# relay-attentuator.net
KiCad netlist of a schematic drawn in EAGLE
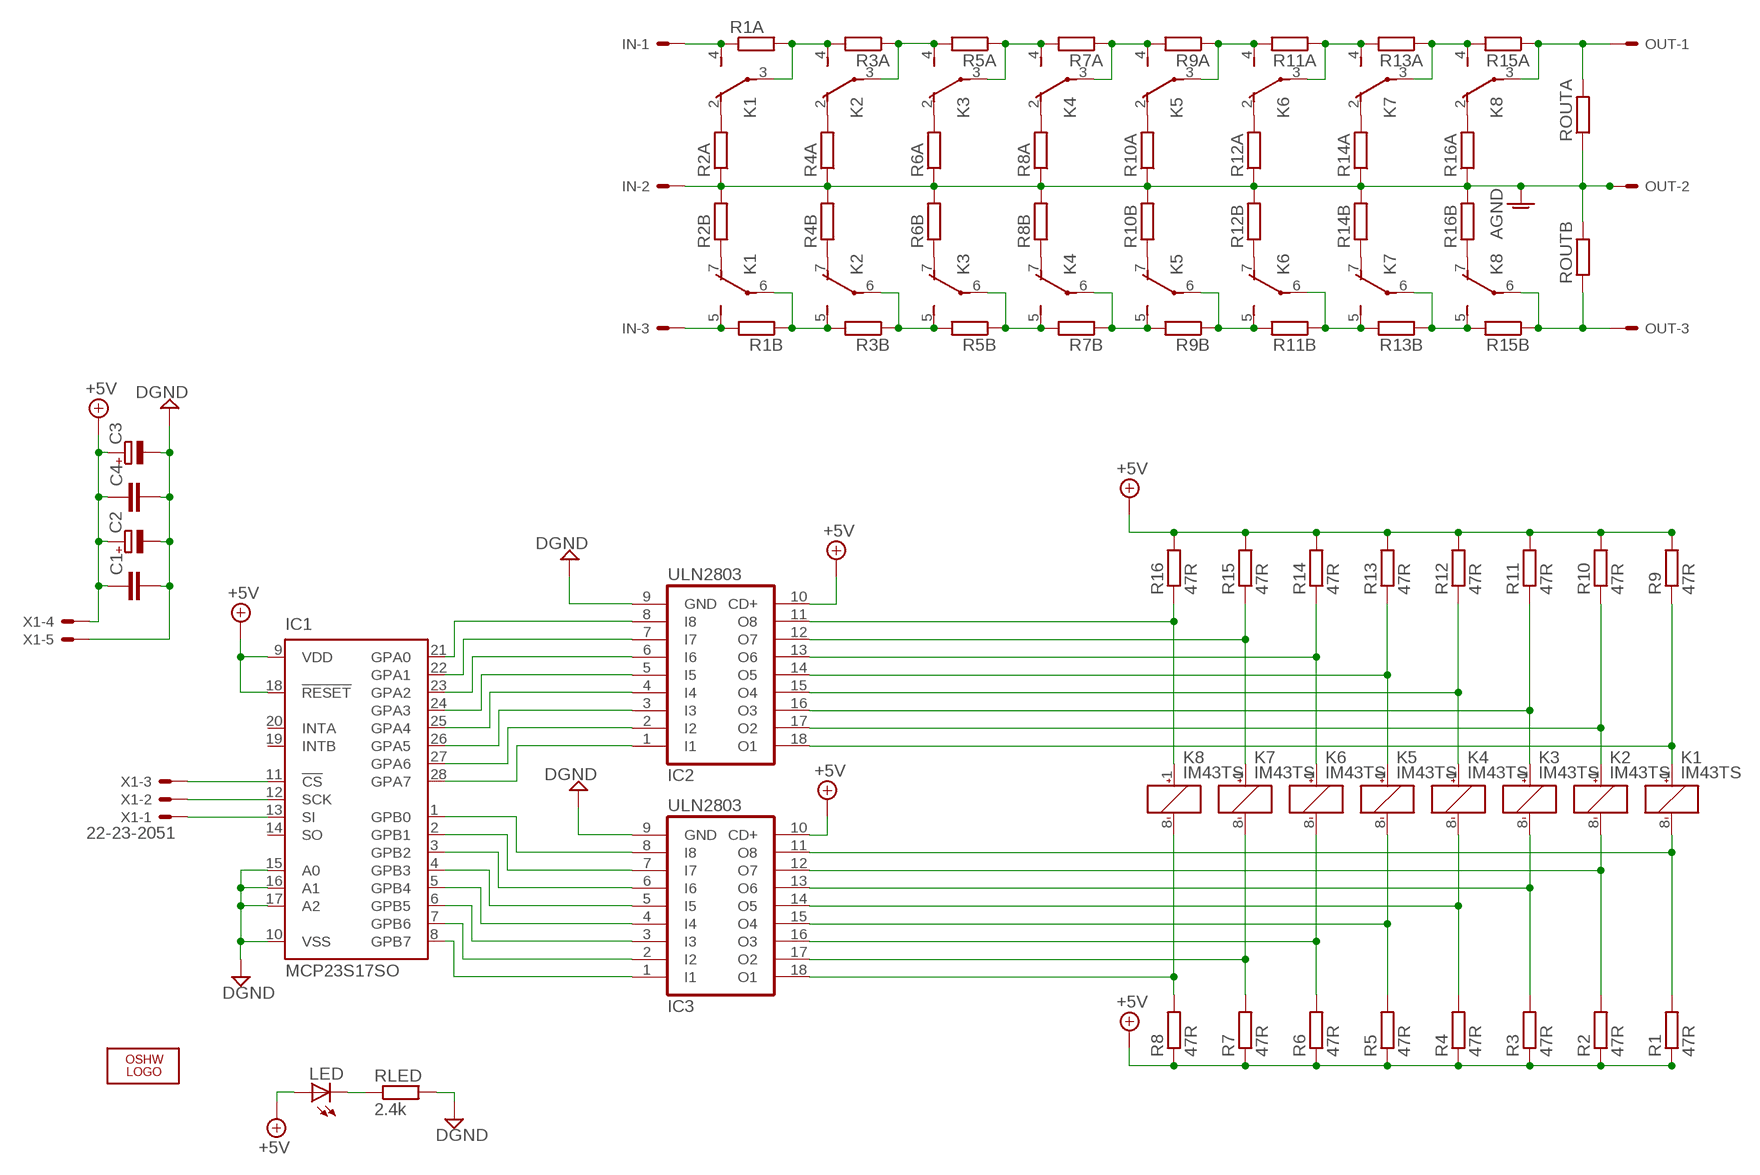
[diagram p0: schematic, sheet 1]

(export (version "E")
  (design (tool "Eeschema 10.0.6"))
  (components
    (comp (ref "C1")
      (value "C-EUC1206")
      (footprint "eagle-import:C1206")
      (libsource (lib "eagle-import") (part "C-EUC1206"))
    )
    (comp (ref "C2")
      (value "CPOL-EUE3.5-8")
      (footprint "eagle-import:E3,5-8")
      (libsource (lib "eagle-import") (part "CPOL-EUE3.5-8"))
    )
    (comp (ref "C3")
      (value "CPOL-EUE3.5-8")
      (footprint "eagle-import:E3,5-8")
      (libsource (lib "eagle-import") (part "CPOL-EUE3.5-8"))
    )
    (comp (ref "C4")
      (value "C-EUC1206")
      (footprint "eagle-import:C1206")
      (libsource (lib "eagle-import") (part "C-EUC1206"))
    )
    (comp (ref "IC1")
      (value "MCP23S17SO")
      (footprint "eagle-import:SO28W")
      (fields (field (name "MF") "MICROCHIP") (field (name "MPN") "MCP23S17-E/SO"))
      (libsource (lib "eagle-import") (part "MCP23S17SO"))
    )
    (comp (ref "IC2")
      (value "ULN2803")
      (footprint "eagle-import:SO-18W")
      (libsource (lib "eagle-import") (part "ULN2803ADW"))
    )
    (comp (ref "IC3")
      (value "ULN2803")
      (footprint "eagle-import:SO-18W")
      (libsource (lib "eagle-import") (part "ULN2803ADW"))
    )
    (comp (ref "IN")
      (value "22-23-2031")
      (footprint "eagle-import:22-23-2031")
      (libsource (lib "eagle-import") (part "22-23-2031"))
    )
    (comp (ref "K1")
      (value "IM43TS")
      (footprint "eagle-import:IM43TS")
      (libsource (lib "eagle-import") (part "IM43TS"))
    )
    (comp (ref "K2")
      (value "IM43TS")
      (footprint "eagle-import:IM43TS")
      (libsource (lib "eagle-import") (part "IM43TS"))
    )
    (comp (ref "K3")
      (value "IM43TS")
      (footprint "eagle-import:IM43TS")
      (libsource (lib "eagle-import") (part "IM43TS"))
    )
    (comp (ref "K4")
      (value "IM43TS")
      (footprint "eagle-import:IM43TS")
      (libsource (lib "eagle-import") (part "IM43TS"))
    )
    (comp (ref "K5")
      (value "IM43TS")
      (footprint "eagle-import:IM43TS")
      (libsource (lib "eagle-import") (part "IM43TS"))
    )
    (comp (ref "K6")
      (value "IM43TS")
      (footprint "eagle-import:IM43TS")
      (libsource (lib "eagle-import") (part "IM43TS"))
    )
    (comp (ref "K7")
      (value "IM43TS")
      (footprint "eagle-import:IM43TS")
      (libsource (lib "eagle-import") (part "IM43TS"))
    )
    (comp (ref "K8")
      (value "IM43TS")
      (footprint "eagle-import:IM43TS")
      (libsource (lib "eagle-import") (part "IM43TS"))
    )
    (comp (ref "LED")
      (value "LEDCHIPLED_1206")
      (footprint "eagle-import:CHIPLED_1206")
      (libsource (lib "eagle-import") (part "LEDCHIPLED_1206"))
    )
    (comp (ref "LOGO1")
      (value "OSHW_LOGO_FILLX0200-NT")
      (footprint "eagle-import:OSHW_FILLX200_NOTEXT")
      (libsource (lib "eagle-import") (part "OSHW_LOGO_FILLX0200-NT"))
    )
    (comp (ref "OUT")
      (value "22-23-2031")
      (footprint "eagle-import:22-23-2031")
      (libsource (lib "eagle-import") (part "22-23-2031"))
    )
    (comp (ref "R1")
      (value "47R")
      (footprint "eagle-import:R1206")
      (libsource (lib "eagle-import") (part "R-EU_R1206"))
    )
    (comp (ref "R1A")
      (value "R-EU_R1206")
      (footprint "eagle-import:R1206")
      (libsource (lib "eagle-import") (part "R-EU_R1206"))
    )
    (comp (ref "R1B")
      (value "R-EU_R1206")
      (footprint "eagle-import:R1206")
      (libsource (lib "eagle-import") (part "R-EU_R1206"))
    )
    (comp (ref "R2")
      (value "47R")
      (footprint "eagle-import:R1206")
      (libsource (lib "eagle-import") (part "R-EU_R1206"))
    )
    (comp (ref "R2A")
      (value "R-EU_R1206")
      (footprint "eagle-import:R1206")
      (libsource (lib "eagle-import") (part "R-EU_R1206"))
    )
    (comp (ref "R2B")
      (value "R-EU_R1206")
      (footprint "eagle-import:R1206")
      (libsource (lib "eagle-import") (part "R-EU_R1206"))
    )
    (comp (ref "R3")
      (value "47R")
      (footprint "eagle-import:R1206")
      (libsource (lib "eagle-import") (part "R-EU_R1206"))
    )
    (comp (ref "R3A")
      (value "R-EU_R1206")
      (footprint "eagle-import:R1206")
      (libsource (lib "eagle-import") (part "R-EU_R1206"))
    )
    (comp (ref "R3B")
      (value "R-EU_R1206")
      (footprint "eagle-import:R1206")
      (libsource (lib "eagle-import") (part "R-EU_R1206"))
    )
    (comp (ref "R4")
      (value "47R")
      (footprint "eagle-import:R1206")
      (libsource (lib "eagle-import") (part "R-EU_R1206"))
    )
    (comp (ref "R4A")
      (value "R-EU_R1206")
      (footprint "eagle-import:R1206")
      (libsource (lib "eagle-import") (part "R-EU_R1206"))
    )
    (comp (ref "R4B")
      (value "R-EU_R1206")
      (footprint "eagle-import:R1206")
      (libsource (lib "eagle-import") (part "R-EU_R1206"))
    )
    (comp (ref "R5")
      (value "47R")
      (footprint "eagle-import:R1206")
      (libsource (lib "eagle-import") (part "R-EU_R1206"))
    )
    (comp (ref "R5A")
      (value "R-EU_R1206")
      (footprint "eagle-import:R1206")
      (libsource (lib "eagle-import") (part "R-EU_R1206"))
    )
    (comp (ref "R5B")
      (value "R-EU_R1206")
      (footprint "eagle-import:R1206")
      (libsource (lib "eagle-import") (part "R-EU_R1206"))
    )
    (comp (ref "R6")
      (value "47R")
      (footprint "eagle-import:R1206")
      (libsource (lib "eagle-import") (part "R-EU_R1206"))
    )
    (comp (ref "R6A")
      (value "R-EU_R1206")
      (footprint "eagle-import:R1206")
      (libsource (lib "eagle-import") (part "R-EU_R1206"))
    )
    (comp (ref "R6B")
      (value "R-EU_R1206")
      (footprint "eagle-import:R1206")
      (libsource (lib "eagle-import") (part "R-EU_R1206"))
    )
    (comp (ref "R7")
      (value "47R")
      (footprint "eagle-import:R1206")
      (libsource (lib "eagle-import") (part "R-EU_R1206"))
    )
    (comp (ref "R7A")
      (value "R-EU_R1206")
      (footprint "eagle-import:R1206")
      (libsource (lib "eagle-import") (part "R-EU_R1206"))
    )
    (comp (ref "R7B")
      (value "R-EU_R1206")
      (footprint "eagle-import:R1206")
      (libsource (lib "eagle-import") (part "R-EU_R1206"))
    )
    (comp (ref "R8")
      (value "47R")
      (footprint "eagle-import:R1206")
      (libsource (lib "eagle-import") (part "R-EU_R1206"))
    )
    (comp (ref "R8A")
      (value "R-EU_R1206")
      (footprint "eagle-import:R1206")
      (libsource (lib "eagle-import") (part "R-EU_R1206"))
    )
    (comp (ref "R8B")
      (value "R-EU_R1206")
      (footprint "eagle-import:R1206")
      (libsource (lib "eagle-import") (part "R-EU_R1206"))
    )
    (comp (ref "R9")
      (value "47R")
      (footprint "eagle-import:R1206")
      (libsource (lib "eagle-import") (part "R-EU_R1206"))
    )
    (comp (ref "R9A")
      (value "R-EU_R1206")
      (footprint "eagle-import:R1206")
      (libsource (lib "eagle-import") (part "R-EU_R1206"))
    )
    (comp (ref "R9B")
      (value "R-EU_R1206")
      (footprint "eagle-import:R1206")
      (libsource (lib "eagle-import") (part "R-EU_R1206"))
    )
    (comp (ref "R10")
      (value "47R")
      (footprint "eagle-import:R1206")
      (libsource (lib "eagle-import") (part "R-EU_R1206"))
    )
    (comp (ref "R10A")
      (value "R-EU_R1206")
      (footprint "eagle-import:R1206")
      (libsource (lib "eagle-import") (part "R-EU_R1206"))
    )
    (comp (ref "R10B")
      (value "R-EU_R1206")
      (footprint "eagle-import:R1206")
      (libsource (lib "eagle-import") (part "R-EU_R1206"))
    )
    (comp (ref "R11")
      (value "47R")
      (footprint "eagle-import:R1206")
      (libsource (lib "eagle-import") (part "R-EU_R1206"))
    )
    (comp (ref "R11A")
      (value "R-EU_R1206")
      (footprint "eagle-import:R1206")
      (libsource (lib "eagle-import") (part "R-EU_R1206"))
    )
    (comp (ref "R11B")
      (value "R-EU_R1206")
      (footprint "eagle-import:R1206")
      (libsource (lib "eagle-import") (part "R-EU_R1206"))
    )
    (comp (ref "R12")
      (value "47R")
      (footprint "eagle-import:R1206")
      (libsource (lib "eagle-import") (part "R-EU_R1206"))
    )
    (comp (ref "R12A")
      (value "R-EU_R1206")
      (footprint "eagle-import:R1206")
      (libsource (lib "eagle-import") (part "R-EU_R1206"))
    )
    (comp (ref "R12B")
      (value "R-EU_R1206")
      (footprint "eagle-import:R1206")
      (libsource (lib "eagle-import") (part "R-EU_R1206"))
    )
    (comp (ref "R13")
      (value "47R")
      (footprint "eagle-import:R1206")
      (libsource (lib "eagle-import") (part "R-EU_R1206"))
    )
    (comp (ref "R13A")
      (value "R-EU_R1206")
      (footprint "eagle-import:R1206")
      (libsource (lib "eagle-import") (part "R-EU_R1206"))
    )
    (comp (ref "R13B")
      (value "R-EU_R1206")
      (footprint "eagle-import:R1206")
      (libsource (lib "eagle-import") (part "R-EU_R1206"))
    )
    (comp (ref "R14")
      (value "47R")
      (footprint "eagle-import:R1206")
      (libsource (lib "eagle-import") (part "R-EU_R1206"))
    )
    (comp (ref "R14A")
      (value "R-EU_R1206")
      (footprint "eagle-import:R1206")
      (libsource (lib "eagle-import") (part "R-EU_R1206"))
    )
    (comp (ref "R14B")
      (value "R-EU_R1206")
      (footprint "eagle-import:R1206")
      (libsource (lib "eagle-import") (part "R-EU_R1206"))
    )
    (comp (ref "R15")
      (value "47R")
      (footprint "eagle-import:R1206")
      (libsource (lib "eagle-import") (part "R-EU_R1206"))
    )
    (comp (ref "R15A")
      (value "R-EU_R1206")
      (footprint "eagle-import:R1206")
      (libsource (lib "eagle-import") (part "R-EU_R1206"))
    )
    (comp (ref "R15B")
      (value "R-EU_R1206")
      (footprint "eagle-import:R1206")
      (libsource (lib "eagle-import") (part "R-EU_R1206"))
    )
    (comp (ref "R16")
      (value "47R")
      (footprint "eagle-import:R1206")
      (libsource (lib "eagle-import") (part "R-EU_R1206"))
    )
    (comp (ref "R16A")
      (value "R-EU_R1206")
      (footprint "eagle-import:R1206")
      (libsource (lib "eagle-import") (part "R-EU_R1206"))
    )
    (comp (ref "R16B")
      (value "R-EU_R1206")
      (footprint "eagle-import:R1206")
      (libsource (lib "eagle-import") (part "R-EU_R1206"))
    )
    (comp (ref "RLED")
      (value "2.4k")
      (footprint "eagle-import:R1206")
      (libsource (lib "eagle-import") (part "R-EU_R1206"))
    )
    (comp (ref "ROUTA")
      (value "R-EU_R1206")
      (footprint "eagle-import:R1206")
      (libsource (lib "eagle-import") (part "R-EU_R1206"))
    )
    (comp (ref "ROUTB")
      (value "R-EU_R1206")
      (footprint "eagle-import:R1206")
      (libsource (lib "eagle-import") (part "R-EU_R1206"))
    )
    (comp (ref "X1")
      (value "22-23-2051")
      (footprint "eagle-import:22-23-2051")
      (fields (field (name "MF") "MOLEX"))
      (libsource (lib "eagle-import") (part "22-23-2051"))
    )
  )
  (nets
    (net (code "1") (name "+5V") (class "Default")
      (node (ref "C1") (pin "1") (pinfunction "1_1") (pintype "passive"))
      (node (ref "C2") (pin "+") (pinfunction "+_+") (pintype "passive"))
      (node (ref "C3") (pin "+") (pinfunction "+_+") (pintype "passive"))
      (node (ref "C4") (pin "1") (pinfunction "1_1") (pintype "passive"))
      (node (ref "IC1") (pin "18") (pinfunction "~{RESET}_18") (pintype "input"))
      (node (ref "IC1") (pin "9") (pinfunction "VDD_9") (pintype "power_in"))
      (node (ref "IC2") (pin "10") (pinfunction "CD+_10") (pintype "passive"))
      (node (ref "IC3") (pin "10") (pinfunction "CD+_10") (pintype "passive"))
      (node (ref "LED") (pin "A") (pinfunction "A_A") (pintype "passive"))
      (node (ref "R1") (pin "1") (pinfunction "1_1") (pintype "passive"))
      (node (ref "R10") (pin "2") (pinfunction "2_2") (pintype "passive"))
      (node (ref "R11") (pin "2") (pinfunction "2_2") (pintype "passive"))
      (node (ref "R12") (pin "2") (pinfunction "2_2") (pintype "passive"))
      (node (ref "R13") (pin "2") (pinfunction "2_2") (pintype "passive"))
      (node (ref "R14") (pin "2") (pinfunction "2_2") (pintype "passive"))
      (node (ref "R15") (pin "2") (pinfunction "2_2") (pintype "passive"))
      (node (ref "R16") (pin "2") (pinfunction "2_2") (pintype "passive"))
      (node (ref "R2") (pin "1") (pinfunction "1_1") (pintype "passive"))
      (node (ref "R3") (pin "1") (pinfunction "1_1") (pintype "passive"))
      (node (ref "R4") (pin "1") (pinfunction "1_1") (pintype "passive"))
      (node (ref "R5") (pin "1") (pinfunction "1_1") (pintype "passive"))
      (node (ref "R6") (pin "1") (pinfunction "1_1") (pintype "passive"))
      (node (ref "R7") (pin "1") (pinfunction "1_1") (pintype "passive"))
      (node (ref "R8") (pin "1") (pinfunction "1_1") (pintype "passive"))
      (node (ref "R9") (pin "2") (pinfunction "2_2") (pintype "passive"))
      (node (ref "X1") (pin "4") (pinfunction "S_4") (pintype "passive"))
    )
    (net (code "2") (name "AGND") (class "Default")
      (node (ref "IN") (pin "2") (pinfunction "S_2") (pintype "passive"))
      (node (ref "OUT") (pin "2") (pinfunction "S_2") (pintype "passive"))
      (node (ref "R10A") (pin "1") (pinfunction "1_1") (pintype "passive"))
      (node (ref "R10B") (pin "2") (pinfunction "2_2") (pintype "passive"))
      (node (ref "R12A") (pin "1") (pinfunction "1_1") (pintype "passive"))
      (node (ref "R12B") (pin "2") (pinfunction "2_2") (pintype "passive"))
      (node (ref "R14A") (pin "1") (pinfunction "1_1") (pintype "passive"))
      (node (ref "R14B") (pin "2") (pinfunction "2_2") (pintype "passive"))
      (node (ref "R16A") (pin "1") (pinfunction "1_1") (pintype "passive"))
      (node (ref "R16B") (pin "2") (pinfunction "2_2") (pintype "passive"))
      (node (ref "R2A") (pin "1") (pinfunction "1_1") (pintype "passive"))
      (node (ref "R2B") (pin "2") (pinfunction "2_2") (pintype "passive"))
      (node (ref "R4A") (pin "1") (pinfunction "1_1") (pintype "passive"))
      (node (ref "R4B") (pin "2") (pinfunction "2_2") (pintype "passive"))
      (node (ref "R6A") (pin "1") (pinfunction "1_1") (pintype "passive"))
      (node (ref "R6B") (pin "2") (pinfunction "2_2") (pintype "passive"))
      (node (ref "R8A") (pin "1") (pinfunction "1_1") (pintype "passive"))
      (node (ref "R8B") (pin "2") (pinfunction "2_2") (pintype "passive"))
      (node (ref "ROUTA") (pin "1") (pinfunction "1_1") (pintype "passive"))
      (node (ref "ROUTB") (pin "2") (pinfunction "2_2") (pintype "passive"))
    )
    (net (code "3") (name "DGND") (class "Default")
      (node (ref "C1") (pin "2") (pinfunction "2_2") (pintype "passive"))
      (node (ref "C2") (pin "-") (pinfunction "-_-") (pintype "passive"))
      (node (ref "C3") (pin "-") (pinfunction "-_-") (pintype "passive"))
      (node (ref "C4") (pin "2") (pinfunction "2_2") (pintype "passive"))
      (node (ref "IC1") (pin "10") (pinfunction "VSS_10") (pintype "power_in"))
      (node (ref "IC1") (pin "15") (pinfunction "A0_15") (pintype "input"))
      (node (ref "IC1") (pin "16") (pinfunction "A1_16") (pintype "input"))
      (node (ref "IC1") (pin "17") (pinfunction "A2_17") (pintype "input"))
      (node (ref "IC2") (pin "9") (pinfunction "GND_9") (pintype "power_in"))
      (node (ref "IC3") (pin "9") (pinfunction "GND_9") (pintype "power_in"))
      (node (ref "RLED") (pin "2") (pinfunction "2_2") (pintype "passive"))
      (node (ref "X1") (pin "5") (pinfunction "S_5") (pintype "passive"))
    )
    (net (code "4") (name "Net-(IC1-GPA0)") (class "Default")
      (node (ref "IC1") (pin "21") (pinfunction "GPA0_21") (pintype "bidirectional"))
      (node (ref "IC2") (pin "8") (pinfunction "I8_8") (pintype "input"))
    )
    (net (code "5") (name "Net-(IC1-GPA1)") (class "Default")
      (node (ref "IC1") (pin "22") (pinfunction "GPA1_22") (pintype "bidirectional"))
      (node (ref "IC2") (pin "7") (pinfunction "I7_7") (pintype "input"))
    )
    (net (code "6") (name "Net-(IC1-GPA2)") (class "Default")
      (node (ref "IC1") (pin "23") (pinfunction "GPA2_23") (pintype "bidirectional"))
      (node (ref "IC2") (pin "6") (pinfunction "I6_6") (pintype "input"))
    )
    (net (code "7") (name "Net-(IC1-GPA3)") (class "Default")
      (node (ref "IC1") (pin "24") (pinfunction "GPA3_24") (pintype "bidirectional"))
      (node (ref "IC2") (pin "5") (pinfunction "I5_5") (pintype "input"))
    )
    (net (code "8") (name "Net-(IC1-GPA4)") (class "Default")
      (node (ref "IC1") (pin "25") (pinfunction "GPA4_25") (pintype "bidirectional"))
      (node (ref "IC2") (pin "4") (pinfunction "I4_4") (pintype "input"))
    )
    (net (code "9") (name "Net-(IC1-GPA5)") (class "Default")
      (node (ref "IC1") (pin "26") (pinfunction "GPA5_26") (pintype "bidirectional"))
      (node (ref "IC2") (pin "3") (pinfunction "I3_3") (pintype "input"))
    )
    (net (code "10") (name "Net-(IC1-GPA6)") (class "Default")
      (node (ref "IC1") (pin "27") (pinfunction "GPA6_27") (pintype "bidirectional"))
      (node (ref "IC2") (pin "2") (pinfunction "I2_2") (pintype "input"))
    )
    (net (code "11") (name "Net-(IC1-GPA7)") (class "Default")
      (node (ref "IC1") (pin "28") (pinfunction "GPA7_28") (pintype "bidirectional"))
      (node (ref "IC2") (pin "1") (pinfunction "I1_1") (pintype "input"))
    )
    (net (code "12") (name "Net-(IC1-GPB0)") (class "Default")
      (node (ref "IC1") (pin "1") (pinfunction "GPB0_1") (pintype "bidirectional"))
      (node (ref "IC3") (pin "8") (pinfunction "I8_8") (pintype "input"))
    )
    (net (code "13") (name "Net-(IC1-GPB1)") (class "Default")
      (node (ref "IC1") (pin "2") (pinfunction "GPB1_2") (pintype "bidirectional"))
      (node (ref "IC3") (pin "7") (pinfunction "I7_7") (pintype "input"))
    )
    (net (code "14") (name "Net-(IC1-GPB2)") (class "Default")
      (node (ref "IC1") (pin "3") (pinfunction "GPB2_3") (pintype "bidirectional"))
      (node (ref "IC3") (pin "6") (pinfunction "I6_6") (pintype "input"))
    )
    (net (code "15") (name "Net-(IC1-GPB3)") (class "Default")
      (node (ref "IC1") (pin "4") (pinfunction "GPB3_4") (pintype "bidirectional"))
      (node (ref "IC3") (pin "5") (pinfunction "I5_5") (pintype "input"))
    )
    (net (code "16") (name "Net-(IC1-GPB4)") (class "Default")
      (node (ref "IC1") (pin "5") (pinfunction "GPB4_5") (pintype "bidirectional"))
      (node (ref "IC3") (pin "4") (pinfunction "I4_4") (pintype "input"))
    )
    (net (code "17") (name "Net-(IC1-GPB5)") (class "Default")
      (node (ref "IC1") (pin "6") (pinfunction "GPB5_6") (pintype "bidirectional"))
      (node (ref "IC3") (pin "3") (pinfunction "I3_3") (pintype "input"))
    )
    (net (code "18") (name "Net-(IC1-GPB6)") (class "Default")
      (node (ref "IC1") (pin "7") (pinfunction "GPB6_7") (pintype "bidirectional"))
      (node (ref "IC3") (pin "2") (pinfunction "I2_2") (pintype "input"))
    )
    (net (code "19") (name "Net-(IC1-GPB7)") (class "Default")
      (node (ref "IC1") (pin "8") (pinfunction "GPB7_8") (pintype "bidirectional"))
      (node (ref "IC3") (pin "1") (pinfunction "I1_1") (pintype "input"))
    )
    (net (code "20") (name "Net-(IC1-SCK)") (class "Default")
      (node (ref "IC1") (pin "12") (pinfunction "SCK_12") (pintype "input"))
      (node (ref "X1") (pin "2") (pinfunction "S_2") (pintype "passive"))
    )
    (net (code "21") (name "Net-(IC1-SI)") (class "Default")
      (node (ref "IC1") (pin "13") (pinfunction "SI_13") (pintype "input"))
      (node (ref "X1") (pin "1") (pinfunction "S_1") (pintype "passive"))
    )
    (net (code "22") (name "Net-(IC1-~{CS})") (class "Default")
      (node (ref "IC1") (pin "11") (pinfunction "~{CS}_11") (pintype "input"))
      (node (ref "X1") (pin "3") (pinfunction "S_3") (pintype "passive"))
    )
    (net (code "23") (name "Net-(IC2-O1)") (class "Default")
      (node (ref "IC2") (pin "18") (pinfunction "O1_18") (pintype "open_collector"))
      (node (ref "K1") (pin "1") (pinfunction "+_1") (pintype "passive"))
      (node (ref "R9") (pin "1") (pinfunction "1_1") (pintype "passive"))
    )
    (net (code "24") (name "Net-(IC2-O2)") (class "Default")
      (node (ref "IC2") (pin "17") (pinfunction "O2_17") (pintype "open_collector"))
      (node (ref "K2") (pin "1") (pinfunction "+_1") (pintype "passive"))
      (node (ref "R10") (pin "1") (pinfunction "1_1") (pintype "passive"))
    )
    (net (code "25") (name "Net-(IC2-O3)") (class "Default")
      (node (ref "IC2") (pin "16") (pinfunction "O3_16") (pintype "open_collector"))
      (node (ref "K3") (pin "1") (pinfunction "+_1") (pintype "passive"))
      (node (ref "R11") (pin "1") (pinfunction "1_1") (pintype "passive"))
    )
    (net (code "26") (name "Net-(IC2-O4)") (class "Default")
      (node (ref "IC2") (pin "15") (pinfunction "O4_15") (pintype "open_collector"))
      (node (ref "K4") (pin "1") (pinfunction "+_1") (pintype "passive"))
      (node (ref "R12") (pin "1") (pinfunction "1_1") (pintype "passive"))
    )
    (net (code "27") (name "Net-(IC2-O5)") (class "Default")
      (node (ref "IC2") (pin "14") (pinfunction "O5_14") (pintype "open_collector"))
      (node (ref "K5") (pin "1") (pinfunction "+_1") (pintype "passive"))
      (node (ref "R13") (pin "1") (pinfunction "1_1") (pintype "passive"))
    )
    (net (code "28") (name "Net-(IC2-O6)") (class "Default")
      (node (ref "IC2") (pin "13") (pinfunction "O6_13") (pintype "open_collector"))
      (node (ref "K6") (pin "1") (pinfunction "+_1") (pintype "passive"))
      (node (ref "R14") (pin "1") (pinfunction "1_1") (pintype "passive"))
    )
    (net (code "29") (name "Net-(IC2-O7)") (class "Default")
      (node (ref "IC2") (pin "12") (pinfunction "O7_12") (pintype "open_collector"))
      (node (ref "K7") (pin "1") (pinfunction "+_1") (pintype "passive"))
      (node (ref "R15") (pin "1") (pinfunction "1_1") (pintype "passive"))
    )
    (net (code "30") (name "Net-(IC2-O8)") (class "Default")
      (node (ref "IC2") (pin "11") (pinfunction "O8_11") (pintype "open_collector"))
      (node (ref "K8") (pin "1") (pinfunction "+_1") (pintype "passive"))
      (node (ref "R16") (pin "1") (pinfunction "1_1") (pintype "passive"))
    )
    (net (code "31") (name "Net-(IC3-O1)") (class "Default")
      (node (ref "IC3") (pin "18") (pinfunction "O1_18") (pintype "open_collector"))
      (node (ref "K8") (pin "8") (pinfunction "-_8") (pintype "passive"))
      (node (ref "R8") (pin "2") (pinfunction "2_2") (pintype "passive"))
    )
    (net (code "32") (name "Net-(IC3-O2)") (class "Default")
      (node (ref "IC3") (pin "17") (pinfunction "O2_17") (pintype "open_collector"))
      (node (ref "K7") (pin "8") (pinfunction "-_8") (pintype "passive"))
      (node (ref "R7") (pin "2") (pinfunction "2_2") (pintype "passive"))
    )
    (net (code "33") (name "Net-(IC3-O3)") (class "Default")
      (node (ref "IC3") (pin "16") (pinfunction "O3_16") (pintype "open_collector"))
      (node (ref "K6") (pin "8") (pinfunction "-_8") (pintype "passive"))
      (node (ref "R6") (pin "2") (pinfunction "2_2") (pintype "passive"))
    )
    (net (code "34") (name "Net-(IC3-O4)") (class "Default")
      (node (ref "IC3") (pin "15") (pinfunction "O4_15") (pintype "open_collector"))
      (node (ref "K5") (pin "8") (pinfunction "-_8") (pintype "passive"))
      (node (ref "R5") (pin "2") (pinfunction "2_2") (pintype "passive"))
    )
    (net (code "35") (name "Net-(IC3-O5)") (class "Default")
      (node (ref "IC3") (pin "14") (pinfunction "O5_14") (pintype "open_collector"))
      (node (ref "K4") (pin "8") (pinfunction "-_8") (pintype "passive"))
      (node (ref "R4") (pin "2") (pinfunction "2_2") (pintype "passive"))
    )
    (net (code "36") (name "Net-(IC3-O6)") (class "Default")
      (node (ref "IC3") (pin "13") (pinfunction "O6_13") (pintype "open_collector"))
      (node (ref "K3") (pin "8") (pinfunction "-_8") (pintype "passive"))
      (node (ref "R3") (pin "2") (pinfunction "2_2") (pintype "passive"))
    )
    (net (code "37") (name "Net-(IC3-O7)") (class "Default")
      (node (ref "IC3") (pin "12") (pinfunction "O7_12") (pintype "open_collector"))
      (node (ref "K2") (pin "8") (pinfunction "-_8") (pintype "passive"))
      (node (ref "R2") (pin "2") (pinfunction "2_2") (pintype "passive"))
    )
    (net (code "38") (name "Net-(IC3-O8)") (class "Default")
      (node (ref "IC3") (pin "11") (pinfunction "O8_11") (pintype "open_collector"))
      (node (ref "K1") (pin "8") (pinfunction "-_8") (pintype "passive"))
      (node (ref "R1") (pin "2") (pinfunction "2_2") (pintype "passive"))
    )
    (net (code "39") (name "Net-(INA-S)") (class "Default")
      (node (ref "IN") (pin "1") (pinfunction "S_1") (pintype "passive"))
      (node (ref "K1") (pin "4") (pinfunction "S_4") (pintype "passive"))
      (node (ref "R1A") (pin "1") (pinfunction "1_1") (pintype "passive"))
    )
    (net (code "40") (name "Net-(INC-S)") (class "Default")
      (node (ref "IN") (pin "3") (pinfunction "S_3") (pintype "passive"))
      (node (ref "K1") (pin "5") (pinfunction "S_5") (pintype "passive"))
      (node (ref "R1B") (pin "2") (pinfunction "2_2") (pintype "passive"))
    )
    (net (code "41") (name "Net-(K1B-O)") (class "Default")
      (node (ref "K1") (pin "2") (pinfunction "O_2") (pintype "passive"))
      (node (ref "R2A") (pin "2") (pinfunction "2_2") (pintype "passive"))
    )
    (net (code "42") (name "Net-(K1B-P)") (class "Default")
      (node (ref "K1") (pin "3") (pinfunction "P_3") (pintype "passive"))
      (node (ref "K2") (pin "4") (pinfunction "S_4") (pintype "passive"))
      (node (ref "R1A") (pin "2") (pinfunction "2_2") (pintype "passive"))
      (node (ref "R3A") (pin "2") (pinfunction "2_2") (pintype "passive"))
    )
    (net (code "43") (name "Net-(K1C-O)") (class "Default")
      (node (ref "K1") (pin "7") (pinfunction "O_7") (pintype "passive"))
      (node (ref "R2B") (pin "1") (pinfunction "1_1") (pintype "passive"))
    )
    (net (code "44") (name "Net-(K1C-P)") (class "Default")
      (node (ref "K1") (pin "6") (pinfunction "P_6") (pintype "passive"))
      (node (ref "K2") (pin "5") (pinfunction "S_5") (pintype "passive"))
      (node (ref "R1B") (pin "1") (pinfunction "1_1") (pintype "passive"))
      (node (ref "R3B") (pin "2") (pinfunction "2_2") (pintype "passive"))
    )
    (net (code "45") (name "Net-(K2B-O)") (class "Default")
      (node (ref "K2") (pin "2") (pinfunction "O_2") (pintype "passive"))
      (node (ref "R4A") (pin "2") (pinfunction "2_2") (pintype "passive"))
    )
    (net (code "46") (name "Net-(K2B-P)") (class "Default")
      (node (ref "K2") (pin "3") (pinfunction "P_3") (pintype "passive"))
      (node (ref "K3") (pin "4") (pinfunction "S_4") (pintype "passive"))
      (node (ref "R3A") (pin "1") (pinfunction "1_1") (pintype "passive"))
      (node (ref "R5A") (pin "2") (pinfunction "2_2") (pintype "passive"))
    )
    (net (code "47") (name "Net-(K2C-O)") (class "Default")
      (node (ref "K2") (pin "7") (pinfunction "O_7") (pintype "passive"))
      (node (ref "R4B") (pin "1") (pinfunction "1_1") (pintype "passive"))
    )
    (net (code "48") (name "Net-(K2C-P)") (class "Default")
      (node (ref "K2") (pin "6") (pinfunction "P_6") (pintype "passive"))
      (node (ref "K3") (pin "5") (pinfunction "S_5") (pintype "passive"))
      (node (ref "R3B") (pin "1") (pinfunction "1_1") (pintype "passive"))
      (node (ref "R5B") (pin "2") (pinfunction "2_2") (pintype "passive"))
    )
    (net (code "49") (name "Net-(K3B-O)") (class "Default")
      (node (ref "K3") (pin "2") (pinfunction "O_2") (pintype "passive"))
      (node (ref "R6A") (pin "2") (pinfunction "2_2") (pintype "passive"))
    )
    (net (code "50") (name "Net-(K3B-P)") (class "Default")
      (node (ref "K3") (pin "3") (pinfunction "P_3") (pintype "passive"))
      (node (ref "K4") (pin "4") (pinfunction "S_4") (pintype "passive"))
      (node (ref "R5A") (pin "1") (pinfunction "1_1") (pintype "passive"))
      (node (ref "R7A") (pin "2") (pinfunction "2_2") (pintype "passive"))
    )
    (net (code "51") (name "Net-(K3C-O)") (class "Default")
      (node (ref "K3") (pin "7") (pinfunction "O_7") (pintype "passive"))
      (node (ref "R6B") (pin "1") (pinfunction "1_1") (pintype "passive"))
    )
    (net (code "52") (name "Net-(K3C-P)") (class "Default")
      (node (ref "K3") (pin "6") (pinfunction "P_6") (pintype "passive"))
      (node (ref "K4") (pin "5") (pinfunction "S_5") (pintype "passive"))
      (node (ref "R5B") (pin "1") (pinfunction "1_1") (pintype "passive"))
      (node (ref "R7B") (pin "2") (pinfunction "2_2") (pintype "passive"))
    )
    (net (code "53") (name "Net-(K4B-O)") (class "Default")
      (node (ref "K4") (pin "2") (pinfunction "O_2") (pintype "passive"))
      (node (ref "R8A") (pin "2") (pinfunction "2_2") (pintype "passive"))
    )
    (net (code "54") (name "Net-(K4B-P)") (class "Default")
      (node (ref "K4") (pin "3") (pinfunction "P_3") (pintype "passive"))
      (node (ref "K5") (pin "4") (pinfunction "S_4") (pintype "passive"))
      (node (ref "R7A") (pin "1") (pinfunction "1_1") (pintype "passive"))
      (node (ref "R9A") (pin "2") (pinfunction "2_2") (pintype "passive"))
    )
    (net (code "55") (name "Net-(K4C-O)") (class "Default")
      (node (ref "K4") (pin "7") (pinfunction "O_7") (pintype "passive"))
      (node (ref "R8B") (pin "1") (pinfunction "1_1") (pintype "passive"))
    )
    (net (code "56") (name "Net-(K4C-P)") (class "Default")
      (node (ref "K4") (pin "6") (pinfunction "P_6") (pintype "passive"))
      (node (ref "K5") (pin "5") (pinfunction "S_5") (pintype "passive"))
      (node (ref "R7B") (pin "1") (pinfunction "1_1") (pintype "passive"))
      (node (ref "R9B") (pin "2") (pinfunction "2_2") (pintype "passive"))
    )
    (net (code "57") (name "Net-(K5B-O)") (class "Default")
      (node (ref "K5") (pin "2") (pinfunction "O_2") (pintype "passive"))
      (node (ref "R10A") (pin "2") (pinfunction "2_2") (pintype "passive"))
    )
    (net (code "58") (name "Net-(K5B-P)") (class "Default")
      (node (ref "K5") (pin "3") (pinfunction "P_3") (pintype "passive"))
      (node (ref "K6") (pin "4") (pinfunction "S_4") (pintype "passive"))
      (node (ref "R11A") (pin "2") (pinfunction "2_2") (pintype "passive"))
      (node (ref "R9A") (pin "1") (pinfunction "1_1") (pintype "passive"))
    )
    (net (code "59") (name "Net-(K5C-O)") (class "Default")
      (node (ref "K5") (pin "7") (pinfunction "O_7") (pintype "passive"))
      (node (ref "R10B") (pin "1") (pinfunction "1_1") (pintype "passive"))
    )
    (net (code "60") (name "Net-(K5C-P)") (class "Default")
      (node (ref "K5") (pin "6") (pinfunction "P_6") (pintype "passive"))
      (node (ref "K6") (pin "5") (pinfunction "S_5") (pintype "passive"))
      (node (ref "R11B") (pin "2") (pinfunction "2_2") (pintype "passive"))
      (node (ref "R9B") (pin "1") (pinfunction "1_1") (pintype "passive"))
    )
    (net (code "61") (name "Net-(K6B-O)") (class "Default")
      (node (ref "K6") (pin "2") (pinfunction "O_2") (pintype "passive"))
      (node (ref "R12A") (pin "2") (pinfunction "2_2") (pintype "passive"))
    )
    (net (code "62") (name "Net-(K6B-P)") (class "Default")
      (node (ref "K6") (pin "3") (pinfunction "P_3") (pintype "passive"))
      (node (ref "K7") (pin "4") (pinfunction "S_4") (pintype "passive"))
      (node (ref "R11A") (pin "1") (pinfunction "1_1") (pintype "passive"))
      (node (ref "R13A") (pin "2") (pinfunction "2_2") (pintype "passive"))
    )
    (net (code "63") (name "Net-(K6C-O)") (class "Default")
      (node (ref "K6") (pin "7") (pinfunction "O_7") (pintype "passive"))
      (node (ref "R12B") (pin "1") (pinfunction "1_1") (pintype "passive"))
    )
    (net (code "64") (name "Net-(K6C-P)") (class "Default")
      (node (ref "K6") (pin "6") (pinfunction "P_6") (pintype "passive"))
      (node (ref "K7") (pin "5") (pinfunction "S_5") (pintype "passive"))
      (node (ref "R11B") (pin "1") (pinfunction "1_1") (pintype "passive"))
      (node (ref "R13B") (pin "2") (pinfunction "2_2") (pintype "passive"))
    )
    (net (code "65") (name "Net-(K7B-O)") (class "Default")
      (node (ref "K7") (pin "2") (pinfunction "O_2") (pintype "passive"))
      (node (ref "R14A") (pin "2") (pinfunction "2_2") (pintype "passive"))
    )
    (net (code "66") (name "Net-(K7B-P)") (class "Default")
      (node (ref "K7") (pin "3") (pinfunction "P_3") (pintype "passive"))
      (node (ref "K8") (pin "4") (pinfunction "S_4") (pintype "passive"))
      (node (ref "R13A") (pin "1") (pinfunction "1_1") (pintype "passive"))
      (node (ref "R15A") (pin "2") (pinfunction "2_2") (pintype "passive"))
    )
    (net (code "67") (name "Net-(K7C-O)") (class "Default")
      (node (ref "K7") (pin "7") (pinfunction "O_7") (pintype "passive"))
      (node (ref "R14B") (pin "1") (pinfunction "1_1") (pintype "passive"))
    )
    (net (code "68") (name "Net-(K7C-P)") (class "Default")
      (node (ref "K7") (pin "6") (pinfunction "P_6") (pintype "passive"))
      (node (ref "K8") (pin "5") (pinfunction "S_5") (pintype "passive"))
      (node (ref "R13B") (pin "1") (pinfunction "1_1") (pintype "passive"))
      (node (ref "R15B") (pin "2") (pinfunction "2_2") (pintype "passive"))
    )
    (net (code "69") (name "Net-(K8B-O)") (class "Default")
      (node (ref "K8") (pin "2") (pinfunction "O_2") (pintype "passive"))
      (node (ref "R16A") (pin "2") (pinfunction "2_2") (pintype "passive"))
    )
    (net (code "70") (name "Net-(K8B-P)") (class "Default")
      (node (ref "K8") (pin "3") (pinfunction "P_3") (pintype "passive"))
      (node (ref "OUT") (pin "1") (pinfunction "S_1") (pintype "passive"))
      (node (ref "R15A") (pin "1") (pinfunction "1_1") (pintype "passive"))
      (node (ref "ROUTA") (pin "2") (pinfunction "2_2") (pintype "passive"))
    )
    (net (code "71") (name "Net-(K8C-O)") (class "Default")
      (node (ref "K8") (pin "7") (pinfunction "O_7") (pintype "passive"))
      (node (ref "R16B") (pin "1") (pinfunction "1_1") (pintype "passive"))
    )
    (net (code "72") (name "Net-(K8C-P)") (class "Default")
      (node (ref "K8") (pin "6") (pinfunction "P_6") (pintype "passive"))
      (node (ref "OUT") (pin "3") (pinfunction "S_3") (pintype "passive"))
      (node (ref "R15B") (pin "1") (pinfunction "1_1") (pintype "passive"))
      (node (ref "ROUTB") (pin "1") (pinfunction "1_1") (pintype "passive"))
    )
    (net (code "73") (name "Net-(LED-PadC)") (class "Default")
      (node (ref "LED") (pin "C") (pinfunction "C_C") (pintype "passive"))
      (node (ref "RLED") (pin "1") (pinfunction "1_1") (pintype "passive"))
    )
    (net (code "74") (name "unconnected-(IC1-INTA-Pad20)") (class "Default")
      (node (ref "IC1") (pin "20") (pinfunction "INTA_20") (pintype "output"))
    )
    (net (code "75") (name "unconnected-(IC1-INTB-Pad19)") (class "Default")
      (node (ref "IC1") (pin "19") (pinfunction "INTB_19") (pintype "output"))
    )
    (net (code "76") (name "unconnected-(IC1-SO-Pad14)") (class "Default")
      (node (ref "IC1") (pin "14") (pinfunction "SO_14") (pintype "output"))
    )
  )
)
